# OTHER_PARTS.net
KiCad netlist of a schematic drawn in Altium Designer
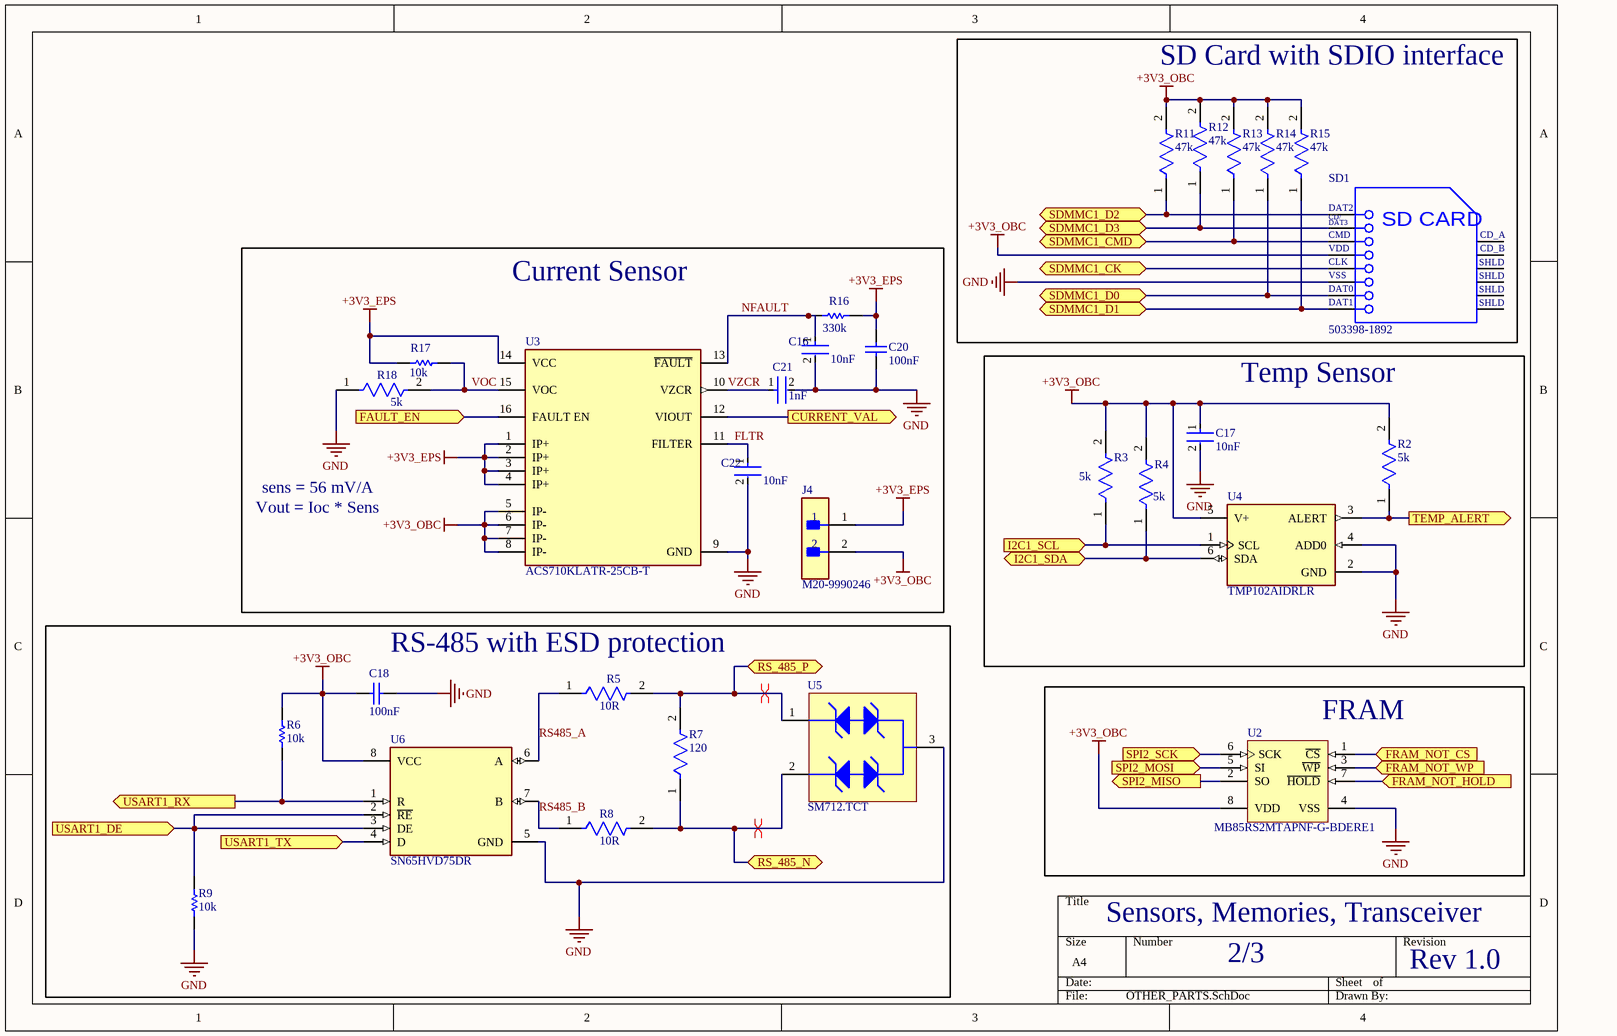
[diagram p0: OTHER_PARTS.SchDoc]

(export (version "E")
  (design (tool "Eeschema 10.0.6"))
  (components
    (comp (ref "C16")
      (value "10nF")
      (footprint "FP-CL165-IPC_C")
      (description "Cap Ceramic 10nF 50V X7R ±10% SMD 0402 +125°C Paper T/R")
      (fields (field (name "VOLTAGE") "50V") (field (name "TOLERANCE") "10%"))
      (libsource (lib "Altium Content Vault") (part "b4654b650e69147ec39a6b967a45e02"))
    )
    (comp (ref "C17")
      (value "10nF")
      (footprint "FP-CL165-IPC_C")
      (description "Cap Ceramic 10nF 50V X7R ±10% SMD 0402 +125°C Paper T/R")
      (fields (field (name "VOLTAGE") "50V") (field (name "TOLERANCE") "10%"))
      (libsource (lib "Altium Content Vault") (part "b4654b650e69147ec39a6b967a45e02"))
    )
    (comp (ref "C18")
      (value "100nF")
      (footprint "SAMS-C0603-2_M")
      (description "Multi-layer Ceramic Capacitor, -55 to 125 degC, 2-Pin SMD (0603), RoHS, Tape and Reel")
      (fields (field (name "MANUFACTURER") "Samsung Electro-Mechanics"))
      (libsource (lib "Altium Content Vault") (part "CAP-NP-2"))
    )
    (comp (ref "C20")
      (value "100nF")
      (footprint "SAMS-C0603-2_M")
      (description "Multi-layer Ceramic Capacitor, -55 to 125 degC, 2-Pin SMD (0603), RoHS, Tape and Reel")
      (fields (field (name "MANUFACTURER") "Samsung Electro-Mechanics"))
      (libsource (lib "Altium Content Vault") (part "CAP-NP-2"))
    )
    (comp (ref "C21")
      (value "1nF")
      (footprint "FP-CC0402-MFG")
      (description "CAP CER 1000PF 50V X7R 0402")
      (fields (field (name "TOLERANCE") "0.1") (field (name "MANUFACTURER") "YAGEO"))
      (libsource (lib "Altium Content Vault") (part "11868f565c42a9108669ba33697ecf6"))
    )
    (comp (ref "C22")
      (value "10nF")
      (footprint "FP-CL165-IPC_C")
      (description "Cap Ceramic 10nF 50V X7R ±10% SMD 0402 +125°C Paper T/R")
      (fields (field (name "VOLTAGE") "50V") (field (name "TOLERANCE") "10%"))
      (libsource (lib "Altium Content Vault") (part "b4654b650e69147ec39a6b967a45e02"))
    )
    (comp (ref "J4")
      (value "M20-9990246")
      (footprint "FP-M20-9990246-MFG")
      (description "CONN HEADER VERT 2POS 2.54MM")
      (fields
        (field (name "OCTOPART") "https://octopart.com/m20-9990246-harwin-2590635")
        (field (name "MANUFACTURER") "Harwin")
      )
      (libsource (lib "Altium Content Vault") (part "3bc925449376181038e59eaffc5286c"))
    )
    (comp (ref "R2")
      (value "5k")
      (footprint "FP-MCR01-MFG")
      (description "Thick Film Chip Resistor, 0402, 5.1kΩ, 1%, 100ppm/°C, 0.063W, 50V")
      (fields (field (name "TOLERANCE") "1%"))
      (libsource (lib "Altium Content Vault") (part "1029c3af85768c4190bb7ad29bc67b5"))
    )
    (comp (ref "R3")
      (value "5k")
      (footprint "FP-MCR01-MFG")
      (description "Thick Film Chip Resistor, 0402, 5.1kΩ, 1%, 100ppm/°C, 0.063W, 50V")
      (fields (field (name "TOLERANCE") "1%"))
      (libsource (lib "Altium Content Vault") (part "1029c3af85768c4190bb7ad29bc67b5"))
    )
    (comp (ref "R4")
      (value "5k")
      (footprint "FP-MCR01-MFG")
      (description "Thick Film Chip Resistor, 0402, 5.1kΩ, 1%, 100ppm/°C, 0.063W, 50V")
      (fields (field (name "TOLERANCE") "1%"))
      (libsource (lib "Altium Content Vault") (part "1029c3af85768c4190bb7ad29bc67b5"))
    )
    (comp (ref "R5")
      (value "10R")
      (footprint "FP-SR0805-MFG")
      (description "RES 10 OHM 1% 1/2W 0805")
      (fields
        (field (name "MANUFACTURER PART NUMBER") "SR0805FR-4710RL")
        (field (name "MANUFACTURER") "Yageo")
      )
      (libsource (lib "Altium Content Vault") (part "1029c3af85768c4190bb7ad29bc67b5"))
    )
    (comp (ref "R6")
      (value "10k")
      (footprint "RESC1608X55X25ML10T15")
      (description "Resistor, 10 KOhm, +/- 5%, 100 mW, -55 to 155 degC, 0603 (1608 Metric), RoHS, Tape and Reel")
      (fields (field (name "MANUFACTURER") "Yageo") (field (name "TOLERANCE") "5%"))
      (libsource (lib "Altium Content Vault") (part "RES-2"))
    )
    (comp (ref "R7")
      (value "120")
      (footprint "FP-AC1206-MFG")
      (description "RES SMD 120 OHM 1% 1/4W 1206")
      (fields
        (field (name "OCTOPART") "https://octopart.com/ac1206fr-07120rl-yageo-30511031")
        (field (name "TOLERANCE") "0.01")
      )
      (libsource (lib "Altium Content Vault") (part "1029c3af85768c4190bb7ad29bc67b5"))
    )
    (comp (ref "R8")
      (value "10R")
      (footprint "FP-SR0805-MFG")
      (description "RES 10 OHM 1% 1/2W 0805")
      (fields
        (field (name "MANUFACTURER PART NUMBER") "SR0805FR-4710RL")
        (field (name "MANUFACTURER") "Yageo")
      )
      (libsource (lib "Altium Content Vault") (part "1029c3af85768c4190bb7ad29bc67b5"))
    )
    (comp (ref "R9")
      (value "10k")
      (footprint "RESC1608X55X25ML10T15")
      (description "Resistor, 10 KOhm, +/- 5%, 100 mW, -55 to 155 degC, 0603 (1608 Metric), RoHS, Tape and Reel")
      (fields (field (name "MANUFACTURER") "Yageo") (field (name "TOLERANCE") "5%"))
      (libsource (lib "Altium Content Vault") (part "RES-2"))
    )
    (comp (ref "R11")
      (value "47k")
      (footprint "FP-MCR01-IPC_C")
      (description "Thick Film Chip Resistor, 0402, 47kΩ, 1%, 100ppm/°C, 0.063W, 50V")
      (fields (field (name "TOLERANCE") "1%"))
      (libsource (lib "Altium Content Vault") (part "1029c3af85768c4190bb7ad29bc67b5"))
    )
    (comp (ref "R12")
      (value "47k")
      (footprint "FP-MCR01-IPC_C")
      (description "Thick Film Chip Resistor, 0402, 47kΩ, 1%, 100ppm/°C, 0.063W, 50V")
      (fields (field (name "TOLERANCE") "1%"))
      (libsource (lib "Altium Content Vault") (part "1029c3af85768c4190bb7ad29bc67b5"))
    )
    (comp (ref "R13")
      (value "47k")
      (footprint "FP-MCR01-IPC_C")
      (description "Thick Film Chip Resistor, 0402, 47kΩ, 1%, 100ppm/°C, 0.063W, 50V")
      (fields (field (name "TOLERANCE") "1%"))
      (libsource (lib "Altium Content Vault") (part "1029c3af85768c4190bb7ad29bc67b5"))
    )
    (comp (ref "R14")
      (value "47k")
      (footprint "FP-MCR01-IPC_C")
      (description "Thick Film Chip Resistor, 0402, 47kΩ, 1%, 100ppm/°C, 0.063W, 50V")
      (fields (field (name "TOLERANCE") "1%"))
      (libsource (lib "Altium Content Vault") (part "1029c3af85768c4190bb7ad29bc67b5"))
    )
    (comp (ref "R15")
      (value "47k")
      (footprint "FP-MCR01-IPC_C")
      (description "Thick Film Chip Resistor, 0402, 47kΩ, 1%, 100ppm/°C, 0.063W, 50V")
      (fields (field (name "TOLERANCE") "1%"))
      (libsource (lib "Altium Content Vault") (part "1029c3af85768c4190bb7ad29bc67b5"))
    )
    (comp (ref "R16")
      (value "330k")
      (footprint "RESC1005X40X25ML05T10")
      (fields (field (name "MANUFACTURER") "Yageo / Phycomp") (field (name "PART NUMBER") "RC0402FR-07330KL"))
      (libsource (lib "Altium Content Vault") (part "RES"))
    )
    (comp (ref "R17")
      (value "10k")
      (footprint "RESC1608X55X25ML10T15")
      (description "Resistor, 10 KOhm, +/- 5%, 100 mW, -55 to 155 degC, 0603 (1608 Metric), RoHS, Tape and Reel")
      (fields (field (name "MANUFACTURER") "Yageo") (field (name "TOLERANCE") "5%"))
      (libsource (lib "Altium Content Vault") (part "RES-2"))
    )
    (comp (ref "R18")
      (value "5k")
      (footprint "FP-MCR01-MFG")
      (description "Thick Film Chip Resistor, 0402, 5.1kΩ, 1%, 100ppm/°C, 0.063W, 50V")
      (fields (field (name "TOLERANCE") "1%"))
      (libsource (lib "Altium Content Vault") (part "1029c3af85768c4190bb7ad29bc67b5"))
    )
    (comp (ref "SD1")
      (value "503398-1892")
      (footprint "MOLX-503398-1892_V")
      (description "Micro SD Connector, Pitch 1.1 mm, 8 Position, Height 1.4 mm, -25 to 85 degC, RoHS, Tape and Reel")
      (fields (field (name "MANUFACTURER") "Molex"))
      (libsource (lib "Altium Content Vault") (part "CN-SD-8-2SW-4S"))
    )
    (comp (ref "U2")
      (value "MB85RS2MTAPNF-G-BDERE1")
      (footprint "CYP-S08.15_M")
      (description "1-Mbit Serial F-RAM, 2 to 3.6 V, -40 to 85 degC, 8-Pin SOIC (S08.15), RoHS, Tube")
      (fields (field (name "GENERIC PART NUMBER") "FM25V10") (field (name "PARTNUMBER") "FM25V10-G"))
      (libsource (lib "Altium Content Vault") (part "CYP-FM25V10-G-8"))
    )
    (comp (ref "U3")
      (value "ACS710KLATR-25CB-T")
      (footprint "FP-LA-16-IPC_C")
      (description "SENSOR CURRENT HALL 25A AC/DC")
      (libsource (lib "Altium Content Vault") (part "cb1b0d90dfd7ccc417fc35895d1ebf9"))
    )
    (comp (ref "U4")
      (value "TMP102AIDRLR")
      (footprint "FP-DRL0006A-MFG")
      (description "SENSOR DIGITAL -40C-125C SOT563")
      (libsource (lib "Altium Content Vault") (part "0dc0cc90889c8b3dc03258d40cf2b82"))
    )
    (comp (ref "U5")
      (value "SM712.TCT")
      (footprint "SMTC-SOT23-3_V")
      (fields (field (name "MANUFACTURER") "Semtech"))
      (libsource (lib "Altium Content Vault") (part "SMTC-SM712.TCT-SOT23-3"))
    )
    (comp (ref "U6")
      (value "SN65HVD75DR")
      (footprint "FP-D0008A-MFG")
      (description "IC TRANSCEIVER HALF 1/1 8SOIC")
      (libsource (lib "Altium Content Vault") (part "886d5080dacc4223fb831ff76299aca"))
    )
  )
  (nets
    (net (code "1") (name "+3V3_EPS") (class "Default")
      (node (ref "C20") (pin "2") (pinfunction "2_2") (pintype "passive"))
      (node (ref "J4") (pin "1") (pinfunction "1_1") (pintype "passive"))
      (node (ref "R16") (pin "2") (pinfunction "2_2") (pintype "passive"))
      (node (ref "R17") (pin "2") (pinfunction "2_2") (pintype "passive"))
      (node (ref "U3") (pin "1") (pinfunction "IP+_1") (pintype "passive"))
      (node (ref "U3") (pin "14") (pinfunction "VCC_14") (pintype "power_in"))
      (node (ref "U3") (pin "2") (pinfunction "IP+_2") (pintype "passive"))
      (node (ref "U3") (pin "3") (pinfunction "IP+_3") (pintype "passive"))
      (node (ref "U3") (pin "4") (pinfunction "IP+_4") (pintype "passive"))
    )
    (net (code "2") (name "+3V3_OBC") (class "Default")
      (node (ref "C17") (pin "1") (pinfunction "1_1") (pintype "passive"))
      (node (ref "C18") (pin "1") (pinfunction "1_1") (pintype "passive"))
      (node (ref "J4") (pin "2") (pinfunction "2_2") (pintype "passive"))
      (node (ref "R11") (pin "2") (pinfunction "2_2") (pintype "passive"))
      (node (ref "R12") (pin "2") (pinfunction "2_2") (pintype "passive"))
      (node (ref "R13") (pin "2") (pinfunction "2_2") (pintype "passive"))
      (node (ref "R14") (pin "2") (pinfunction "2_2") (pintype "passive"))
      (node (ref "R15") (pin "2") (pinfunction "2_2") (pintype "passive"))
      (node (ref "R2") (pin "2") (pinfunction "2_2") (pintype "passive"))
      (node (ref "R3") (pin "2") (pinfunction "2_2") (pintype "passive"))
      (node (ref "R4") (pin "2") (pinfunction "2_2") (pintype "passive"))
      (node (ref "R6") (pin "2") (pinfunction "2_2") (pintype "passive"))
      (node (ref "SD1") (pin "4") (pinfunction "VDD_4") (pintype "passive"))
      (node (ref "U2") (pin "8") (pinfunction "VDD_8") (pintype "power_in"))
      (node (ref "U3") (pin "5") (pinfunction "IP-_5") (pintype "passive"))
      (node (ref "U3") (pin "6") (pinfunction "IP-_6") (pintype "passive"))
      (node (ref "U3") (pin "7") (pinfunction "IP-_7") (pintype "passive"))
      (node (ref "U3") (pin "8") (pinfunction "IP-_8") (pintype "passive"))
      (node (ref "U4") (pin "5") (pinfunction "V+_5") (pintype "power_in"))
      (node (ref "U6") (pin "8") (pinfunction "VCC_8") (pintype "power_in"))
    )
    (net (code "3") (name "/CURRENT_VAL") (class "Default")
      (node (ref "U3") (pin "12") (pinfunction "VIOUT_12") (pintype "passive"))
    )
    (net (code "4") (name "/FAULT_EN") (class "Default")
      (node (ref "U3") (pin "16") (pinfunction "FAULT_EN_16") (pintype "passive"))
    )
    (net (code "5") (name "/FLTR") (class "Default")
      (node (ref "C22") (pin "1") (pinfunction "1_1") (pintype "passive"))
      (node (ref "U3") (pin "11") (pinfunction "FILTER_11") (pintype "passive"))
    )
    (net (code "6") (name "/FRAM_NOT_CS") (class "Default")
      (node (ref "U2") (pin "1") (pinfunction "~{CS}_1") (pintype "input"))
    )
    (net (code "7") (name "/FRAM_NOT_HOLD") (class "Default")
      (node (ref "U2") (pin "7") (pinfunction "~{HOLD}_7") (pintype "input"))
    )
    (net (code "8") (name "/FRAM_NOT_WP") (class "Default")
      (node (ref "U2") (pin "3") (pinfunction "~{WP}_3") (pintype "input"))
    )
    (net (code "9") (name "/I2C1_SCL") (class "Default")
      (node (ref "R3") (pin "1") (pinfunction "1_1") (pintype "passive"))
      (node (ref "U4") (pin "1") (pinfunction "SCL_1") (pintype "input"))
    )
    (net (code "10") (name "/I2C1_SDA") (class "Default")
      (node (ref "R4") (pin "1") (pinfunction "1_1") (pintype "passive"))
      (node (ref "U4") (pin "6") (pinfunction "SDA_6") (pintype "bidirectional"))
    )
    (net (code "11") (name "/NFAULT") (class "Default")
      (node (ref "C16") (pin "1") (pinfunction "1_1") (pintype "passive"))
      (node (ref "R16") (pin "1") (pinfunction "1_1") (pintype "passive"))
      (node (ref "U3") (pin "13") (pinfunction "~{FAULT}_13") (pintype "passive"))
    )
    (net (code "12") (name "/RS485_A") (class "Default")
      (node (ref "R5") (pin "1") (pinfunction "1_1") (pintype "passive"))
      (node (ref "U6") (pin "6") (pinfunction "A_6") (pintype "bidirectional"))
    )
    (net (code "13") (name "/RS485_B") (class "Default")
      (node (ref "R8") (pin "1") (pinfunction "1_1") (pintype "passive"))
      (node (ref "U6") (pin "7") (pinfunction "B_7") (pintype "bidirectional"))
    )
    (net (code "14") (name "/RS_485_N") (class "Default")
      (node (ref "R7") (pin "1") (pinfunction "1_1") (pintype "passive"))
      (node (ref "R8") (pin "2") (pinfunction "2_2") (pintype "passive"))
      (node (ref "U5") (pin "2") (pinfunction "2_2") (pintype "passive"))
    )
    (net (code "15") (name "/RS_485_P") (class "Default")
      (node (ref "R5") (pin "2") (pinfunction "2_2") (pintype "passive"))
      (node (ref "R7") (pin "2") (pinfunction "2_2") (pintype "passive"))
      (node (ref "U5") (pin "1") (pinfunction "1_1") (pintype "passive"))
    )
    (net (code "16") (name "/SDMMC1_CK") (class "Default")
      (node (ref "SD1") (pin "5") (pinfunction "CLK_5") (pintype "passive"))
    )
    (net (code "17") (name "/SDMMC1_CMD") (class "Default")
      (node (ref "R13") (pin "1") (pinfunction "1_1") (pintype "passive"))
      (node (ref "SD1") (pin "3") (pinfunction "CMD_3") (pintype "passive"))
    )
    (net (code "18") (name "/SDMMC1_D0") (class "Default")
      (node (ref "R14") (pin "1") (pinfunction "1_1") (pintype "passive"))
      (node (ref "SD1") (pin "7") (pinfunction "DAT0_7") (pintype "passive"))
    )
    (net (code "19") (name "/SDMMC1_D1") (class "Default")
      (node (ref "R15") (pin "1") (pinfunction "1_1") (pintype "passive"))
      (node (ref "SD1") (pin "8") (pinfunction "DAT1_8") (pintype "passive"))
    )
    (net (code "20") (name "/SDMMC1_D2") (class "Default")
      (node (ref "R11") (pin "1") (pinfunction "1_1") (pintype "passive"))
      (node (ref "SD1") (pin "1") (pinfunction "DAT2_1") (pintype "passive"))
    )
    (net (code "21") (name "/SDMMC1_D3") (class "Default")
      (node (ref "R12") (pin "1") (pinfunction "1_1") (pintype "passive"))
      (node (ref "SD1") (pin "2") (pinfunction "CD/DAT3_2") (pintype "passive"))
    )
    (net (code "22") (name "/SPI2_MISO") (class "Default")
      (node (ref "U2") (pin "2") (pinfunction "SO_2") (pintype "tri_state"))
    )
    (net (code "23") (name "/SPI2_MOSI") (class "Default")
      (node (ref "U2") (pin "5") (pinfunction "SI_5") (pintype "input"))
    )
    (net (code "24") (name "/SPI2_SCK") (class "Default")
      (node (ref "U2") (pin "6") (pinfunction "SCK_6") (pintype "input"))
    )
    (net (code "25") (name "/TEMP_ALERT") (class "Default")
      (node (ref "R2") (pin "1") (pinfunction "1_1") (pintype "passive"))
      (node (ref "U4") (pin "3") (pinfunction "ALERT_3") (pintype "output"))
    )
    (net (code "26") (name "/USART1_DE") (class "Default")
      (node (ref "R9") (pin "2") (pinfunction "2_2") (pintype "passive"))
      (node (ref "U6") (pin "2") (pinfunction "~{RE}_2") (pintype "input"))
      (node (ref "U6") (pin "3") (pinfunction "DE_3") (pintype "input"))
    )
    (net (code "27") (name "/USART1_RX") (class "Default")
      (node (ref "R6") (pin "1") (pinfunction "1_1") (pintype "passive"))
      (node (ref "U6") (pin "1") (pinfunction "R_1") (pintype "input"))
    )
    (net (code "28") (name "/USART1_TX") (class "Default")
      (node (ref "U6") (pin "4") (pinfunction "D_4") (pintype "input"))
    )
    (net (code "29") (name "/VOC") (class "Default")
      (node (ref "R17") (pin "1") (pinfunction "1_1") (pintype "passive"))
      (node (ref "R18") (pin "2") (pinfunction "2_2") (pintype "passive"))
      (node (ref "U3") (pin "15") (pinfunction "VOC_15") (pintype "passive"))
    )
    (net (code "30") (name "/VZCR") (class "Default")
      (node (ref "C21") (pin "1") (pinfunction "1_1") (pintype "passive"))
      (node (ref "U3") (pin "10") (pinfunction "VZCR_10") (pintype "output"))
    )
    (net (code "31") (name "GND") (class "Default")
      (node (ref "C16") (pin "2") (pinfunction "2_2") (pintype "passive"))
      (node (ref "C17") (pin "2") (pinfunction "2_2") (pintype "passive"))
      (node (ref "C18") (pin "2") (pinfunction "2_2") (pintype "passive"))
      (node (ref "C20") (pin "1") (pinfunction "1_1") (pintype "passive"))
      (node (ref "C21") (pin "2") (pinfunction "2_2") (pintype "passive"))
      (node (ref "C22") (pin "2") (pinfunction "2_2") (pintype "passive"))
      (node (ref "R18") (pin "1") (pinfunction "1_1") (pintype "passive"))
      (node (ref "R9") (pin "1") (pinfunction "1_1") (pintype "passive"))
      (node (ref "SD1") (pin "6") (pinfunction "VSS_6") (pintype "passive"))
      (node (ref "U2") (pin "4") (pinfunction "VSS_4") (pintype "power_in"))
      (node (ref "U3") (pin "9") (pinfunction "GND_9") (pintype "power_in"))
      (node (ref "U4") (pin "2") (pinfunction "GND_2") (pintype "power_in"))
      (node (ref "U4") (pin "4") (pinfunction "ADD0_4") (pintype "input"))
      (node (ref "U5") (pin "3") (pinfunction "3_3") (pintype "passive"))
      (node (ref "U6") (pin "5") (pinfunction "GND_5") (pintype "power_in"))
    )
    (net (code "32") (name "unconnected-(SD1-CD_A-Pad9)") (class "Default")
      (node (ref "SD1") (pin "9") (pinfunction "CD_A_9") (pintype "passive"))
    )
    (net (code "33") (name "unconnected-(SD1-CD_B-Pad10)") (class "Default")
      (node (ref "SD1") (pin "10") (pinfunction "CD_B_10") (pintype "passive"))
    )
    (net (code "34") (name "unconnected-(SD1-SHLD-Pad11)") (class "Default")
      (node (ref "SD1") (pin "11") (pinfunction "SHLD_11") (pintype "passive"))
    )
    (net (code "35") (name "unconnected-(SD1-SHLD-Pad12)") (class "Default")
      (node (ref "SD1") (pin "12") (pinfunction "SHLD_12") (pintype "passive"))
    )
    (net (code "36") (name "unconnected-(SD1-SHLD-Pad13)") (class "Default")
      (node (ref "SD1") (pin "13") (pinfunction "SHLD_13") (pintype "passive"))
    )
    (net (code "37") (name "unconnected-(SD1-SHLD-Pad14)") (class "Default")
      (node (ref "SD1") (pin "14") (pinfunction "SHLD_14") (pintype "passive"))
    )
  )
)
